# Esquematico_VitaLink.net
KiCad netlist of a schematic drawn in Altium Designer
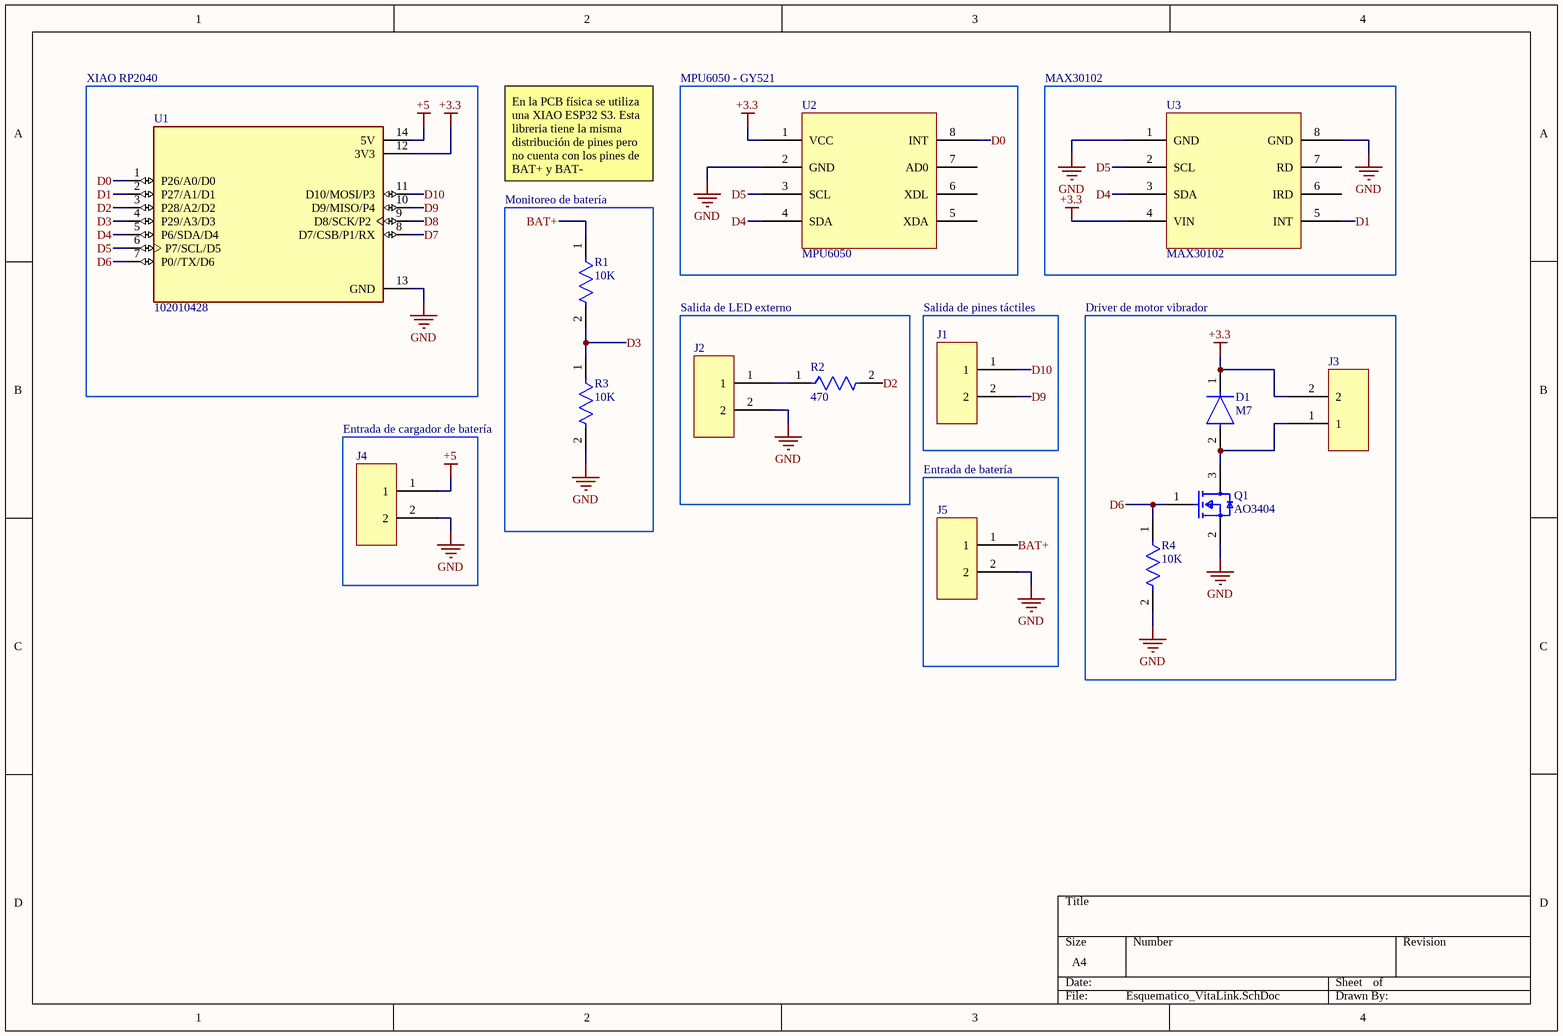
[diagram p0: Esquematico_VitaLink.SchDoc]

(export (version "E")
  (design (tool "Eeschema 10.0.6"))
  (components
    (comp (ref "D1")
      (value "M7")
      (footprint "FP-403AE-MFG")
      (description "ES1H Rectifier Diode, 1 Phase, 1 Element, 1A, 500V V(RRM), Silicon, DO-214AC")
      (libsource (lib "Altium Content Vault") (part "d7152d700b627762746794eb795d46e"))
    )
    (comp (ref "J1")
      (value "Component_1")
      (footprint "WireConnector:PCBComponent_1")
      (libsource (lib "") (part "Component_1_1"))
    )
    (comp (ref "J2")
      (value "Component_1")
      (footprint "WireConnector:PCBComponent_1")
      (libsource (lib "") (part "Component_1_1"))
    )
    (comp (ref "J3")
      (value "Component_1")
      (footprint "WireConnector:PCBComponent_1")
      (libsource (lib "WireConnector") (part "Component_1"))
    )
    (comp (ref "J4")
      (value "Component_1")
      (footprint "WireConnector:PCBComponent_1")
      (libsource (lib "") (part "Component_1_1"))
    )
    (comp (ref "J5")
      (value "Component_1")
      (footprint "WireConnector:PCBComponent_1")
      (libsource (lib "") (part "Component_1_1"))
    )
    (comp (ref "Q1")
      (value "AO3404")
      (footprint "FP-318-08-IPC_B")
      (description "MOSFET N-CH 50V 220MA SOT-23")
      (libsource (lib "Altium Content Vault") (part "3b9c635fedb024a5347a57b145af9cc"))
    )
    (comp (ref "R1")
      (value "10K")
      (footprint "FP-RG2012-IPC_B")
      (description "Automotive Metal Thin Film Chip Resistor, 0805, 470Ω, 0.1%, 25ppm/°C, 0.125W, 150V")
      (fields (field (name "TOLERANCE") "0.1%"))
      (libsource (lib "Altium Content Vault") (part "1029c3af85768c4190bb7ad29bc67b5"))
    )
    (comp (ref "R2")
      (value "470")
      (footprint "FP-RG2012-IPC_B")
      (description "Automotive Metal Thin Film Chip Resistor, 0805, 470Ω, 0.1%, 25ppm/°C, 0.125W, 150V")
      (fields (field (name "TOLERANCE") "0.1%"))
      (libsource (lib "Altium Content Vault") (part "1029c3af85768c4190bb7ad29bc67b5"))
    )
    (comp (ref "R3")
      (value "10K")
      (footprint "FP-RG2012-IPC_B")
      (description "Automotive Metal Thin Film Chip Resistor, 0805, 470Ω, 0.1%, 25ppm/°C, 0.125W, 150V")
      (fields (field (name "TOLERANCE") "0.1%"))
      (libsource (lib "Altium Content Vault") (part "1029c3af85768c4190bb7ad29bc67b5"))
    )
    (comp (ref "R4")
      (value "10K")
      (footprint "FP-RG2012-IPC_B")
      (description "Automotive Metal Thin Film Chip Resistor, 0805, 470Ω, 0.1%, 25ppm/°C, 0.125W, 150V")
      (fields (field (name "TOLERANCE") "0.1%"))
      (libsource (lib "Altium Content Vault") (part "1029c3af85768c4190bb7ad29bc67b5"))
    )
    (comp (ref "U1")
      (value "102010428")
      (footprint "MODULE_102010428")
      (description "RP2040 XIAO RP2040 series ARMÂ® CortexÂ®-M0+ MCU 32-Bit Embedded Evaluation Board")
      (fields (field (name "MF") "Seeed Technology Co., Ltd"))
      (libsource (lib "XIAO-RP2040") (part "102010428"))
    )
    (comp (ref "U2")
      (value "MPU6050")
      (footprint "PCBComponent_1")
      (libsource (lib "MPU6050-GY521") (part "Component_1"))
    )
    (comp (ref "U3")
      (value "MAX30102")
      (footprint "MAX30102:PCBComponent_1")
      (libsource (lib "MAX30102") (part "Component_1"))
    )
  )
  (nets
    (net (code "1") (name "+3.3") (class "Default")
      (node (ref "D1") (pin "1") (pinfunction "C_1") (pintype "passive"))
      (node (ref "J3") (pin "2") (pinfunction "2_2") (pintype "passive"))
      (node (ref "U1") (pin "12") (pinfunction "3V3_12") (pintype "power_in"))
      (node (ref "U2") (pin "1") (pinfunction "VCC_1") (pintype "passive"))
      (node (ref "U3") (pin "4") (pinfunction "VIN_4") (pintype "passive"))
    )
    (net (code "2") (name "+5") (class "Default")
      (node (ref "J4") (pin "1") (pinfunction "1_1") (pintype "passive"))
      (node (ref "U1") (pin "14") (pinfunction "5V_14") (pintype "power_in"))
    )
    (net (code "3") (name "/BAT+") (class "Default")
      (node (ref "J5") (pin "1") (pinfunction "1_1") (pintype "passive"))
      (node (ref "R1") (pin "1") (pinfunction "1_1") (pintype "passive"))
    )
    (net (code "4") (name "/D0") (class "Default")
      (node (ref "U1") (pin "1") (pinfunction "P26/A0/D0_1") (pintype "bidirectional"))
      (node (ref "U2") (pin "8") (pinfunction "INT_8") (pintype "passive"))
    )
    (net (code "5") (name "/D1") (class "Default")
      (node (ref "U1") (pin "2") (pinfunction "P27/A1/D1_2") (pintype "bidirectional"))
      (node (ref "U3") (pin "5") (pinfunction "INT_5") (pintype "passive"))
    )
    (net (code "6") (name "/D2") (class "Default")
      (node (ref "R2") (pin "2") (pinfunction "2_2") (pintype "passive"))
      (node (ref "U1") (pin "3") (pinfunction "P28/A2/D2_3") (pintype "bidirectional"))
    )
    (net (code "7") (name "/D3") (class "Default")
      (node (ref "R1") (pin "2") (pinfunction "2_2") (pintype "passive"))
      (node (ref "R3") (pin "1") (pinfunction "1_1") (pintype "passive"))
      (node (ref "U1") (pin "4") (pinfunction "P29/A3/D3_4") (pintype "bidirectional"))
    )
    (net (code "8") (name "/D4") (class "Default")
      (node (ref "U1") (pin "5") (pinfunction "P6/SDA/D4_5") (pintype "bidirectional"))
      (node (ref "U2") (pin "4") (pinfunction "SDA_4") (pintype "passive"))
      (node (ref "U3") (pin "3") (pinfunction "SDA_3") (pintype "passive"))
    )
    (net (code "9") (name "/D5") (class "Default")
      (node (ref "U1") (pin "6") (pinfunction "P7/SCL/D5_6") (pintype "bidirectional"))
      (node (ref "U2") (pin "3") (pinfunction "SCL_3") (pintype "passive"))
      (node (ref "U3") (pin "2") (pinfunction "SCL_2") (pintype "passive"))
    )
    (net (code "10") (name "/D6") (class "Default")
      (node (ref "Q1") (pin "1") (pinfunction "G_1") (pintype "passive"))
      (node (ref "R4") (pin "1") (pinfunction "1_1") (pintype "passive"))
      (node (ref "U1") (pin "7") (pinfunction "P0//TX/D6_7") (pintype "bidirectional"))
    )
    (net (code "11") (name "/D7") (class "Default")
      (node (ref "U1") (pin "8") (pinfunction "D7/CSB/P1/RX_8") (pintype "bidirectional"))
    )
    (net (code "12") (name "/D8") (class "Default")
      (node (ref "U1") (pin "9") (pinfunction "D8/SCK/P2_9") (pintype "bidirectional"))
    )
    (net (code "13") (name "/D9") (class "Default")
      (node (ref "J1") (pin "2") (pinfunction "2_2") (pintype "passive"))
      (node (ref "U1") (pin "10") (pinfunction "D9/MISO/P4_10") (pintype "bidirectional"))
    )
    (net (code "14") (name "/D10") (class "Default")
      (node (ref "J1") (pin "1") (pinfunction "1_1") (pintype "passive"))
      (node (ref "U1") (pin "11") (pinfunction "D10/MOSI/P3_11") (pintype "bidirectional"))
    )
    (net (code "15") (name "GND") (class "Default")
      (node (ref "J2") (pin "2") (pinfunction "2_2") (pintype "passive"))
      (node (ref "J4") (pin "2") (pinfunction "2_2") (pintype "passive"))
      (node (ref "J5") (pin "2") (pinfunction "2_2") (pintype "passive"))
      (node (ref "Q1") (pin "2") (pinfunction "S_2") (pintype "passive"))
      (node (ref "R3") (pin "2") (pinfunction "2_2") (pintype "passive"))
      (node (ref "R4") (pin "2") (pinfunction "2_2") (pintype "passive"))
      (node (ref "U1") (pin "13") (pinfunction "GND_13") (pintype "power_in"))
      (node (ref "U2") (pin "2") (pinfunction "GND_2") (pintype "passive"))
      (node (ref "U3") (pin "1") (pinfunction "GND_1") (pintype "passive"))
      (node (ref "U3") (pin "8") (pinfunction "GND_8") (pintype "passive"))
    )
    (net (code "16") (name "Net-(D1-A)") (class "Default")
      (node (ref "D1") (pin "2") (pinfunction "A_2") (pintype "passive"))
      (node (ref "J3") (pin "1") (pinfunction "1_1") (pintype "passive"))
      (node (ref "Q1") (pin "3") (pinfunction "D_3") (pintype "passive"))
    )
    (net (code "17") (name "Net-(J2-Pad1)") (class "Default")
      (node (ref "J2") (pin "1") (pinfunction "1_1") (pintype "passive"))
      (node (ref "R2") (pin "1") (pinfunction "1_1") (pintype "passive"))
    )
    (net (code "18") (name "unconnected-(U2-AD0-Pad7)") (class "Default")
      (node (ref "U2") (pin "7") (pinfunction "AD0_7") (pintype "passive"))
    )
    (net (code "19") (name "unconnected-(U2-XDA-Pad5)") (class "Default")
      (node (ref "U2") (pin "5") (pinfunction "XDA_5") (pintype "passive"))
    )
    (net (code "20") (name "unconnected-(U2-XDL-Pad6)") (class "Default")
      (node (ref "U2") (pin "6") (pinfunction "XDL_6") (pintype "passive"))
    )
    (net (code "21") (name "unconnected-(U3-IRD-Pad6)") (class "Default")
      (node (ref "U3") (pin "6") (pinfunction "IRD_6") (pintype "passive"))
    )
    (net (code "22") (name "unconnected-(U3-RD-Pad7)") (class "Default")
      (node (ref "U3") (pin "7") (pinfunction "RD_7") (pintype "passive"))
    )
  )
)
